# LPCB235_-_HE_ISO_CHANNEL.net
KiCad netlist of a schematic drawn in Altium Designer
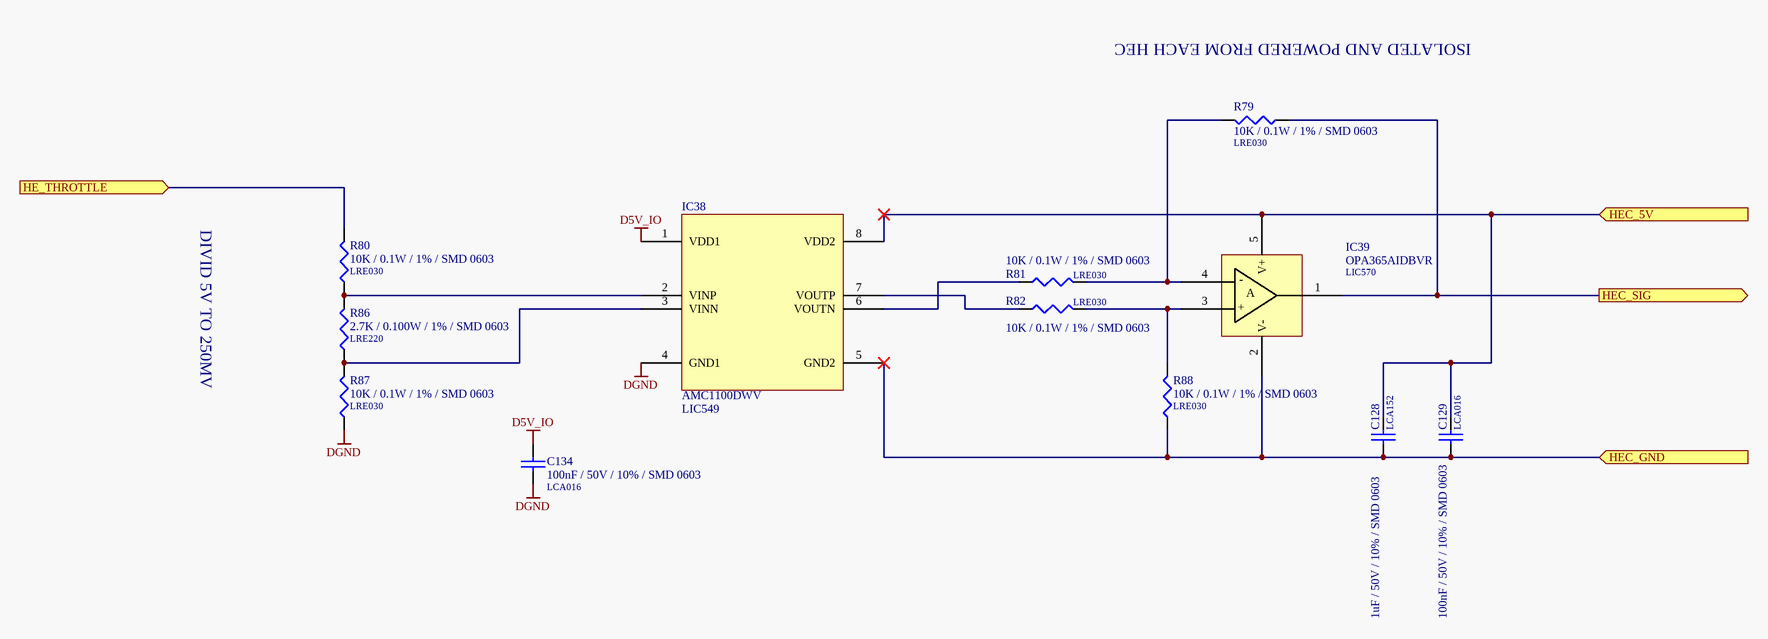
[diagram p0: LPCB235 - HE ISO CHANNEL.SchDoc]

(export (version "E")
  (design (tool "Eeschema 10.0.6"))
  (components
    (comp (ref "C128")
      (value "1uF / 50V / 10% / SMD 0603")
      (footprint "LFP011__CC1608-0603-IPC7351_B")
      (description "Capacitor, Ceramic Chip, 1uF, 50V, 10% (X5R), SMD 0603 [LCA152]")
      (fields (field (name "LDL_NUMBER") "LCA152"))
      (libsource (lib "LDL_Capacitors") (part "1uF / 50V / 10% / SMD 0603"))
    )
    (comp (ref "C129")
      (value "100nF / 50V / 10% / SMD 0603")
      (footprint "LFP011__CC1608-0603-IPC7351_B")
      (description "Capacitor, Ceramic Chip, 100nF (0.1uF), 50V, 5%, SMD 0603 [LCA016]")
      (fields (field (name "LDL_NUMBER") "LCA016"))
      (libsource (lib "LDL_Capacitors") (part "100nF / 50V / 10% / SMD 0603"))
    )
    (comp (ref "C134")
      (value "100nF / 50V / 10% / SMD 0603")
      (footprint "LFP011__CC1608-0603-IPC7351_B")
      (description "Capacitor, Ceramic Chip, 100nF (0.1uF), 50V, 5%, SMD 0603 [LCA016]")
      (fields (field (name "LDL_NUMBER") "LCA016"))
      (libsource (lib "LDL_Capacitors") (part "100nF / 50V / 10% / SMD 0603"))
    )
    (comp (ref "IC38")
      (value "AMC1100DWV")
      (footprint "LFP150__DWV0008A")
      (description "IC, Isolation Amplifier, SMD SOIC8 [LIC549]")
      (fields (field (name "LDL_NUMBER") "LIC549"))
      (libsource (lib "LDL_Semiconductors") (part "AMC1100DWV"))
    )
    (comp (ref "IC39")
      (value "OPA365AIDBVR")
      (footprint "LFP114__R-PDSO-G5")
      (description "IC, OpAmp, 1-Channel, Low Noise, SMD SOT-23-5 [LIC570]")
      (fields (field (name "LDL_NUMBER") "LIC570"))
      (libsource (lib "LDL_Semiconductors") (part "OPA365AIDBVR"))
    )
    (comp (ref "R79")
      (value "10K / 0.1W / 1% / SMD 0603")
      (footprint "LFP020__CR1608-0603-IPC7351_B")
      (description "Resistor, Ceramic Chip, 10K, 0.1W, 1%, SMD 0603 [LRE030]")
      (fields (field (name "LDL_NUMBER") "LRE030"))
      (libsource (lib "LDL_Resistors") (part "10K / 0.1W / 1% / SMD 0603"))
    )
    (comp (ref "R80")
      (value "10K / 0.1W / 1% / SMD 0603")
      (footprint "LFP020__CR1608-0603-IPC7351_B")
      (description "Resistor, Ceramic Chip, 10K, 0.1W, 1%, SMD 0603 [LRE030]")
      (fields (field (name "LDL_NUMBER") "LRE030"))
      (libsource (lib "LDL_Resistors") (part "10K / 0.1W / 1% / SMD 0603"))
    )
    (comp (ref "R81")
      (value "10K / 0.1W / 1% / SMD 0603")
      (footprint "LFP020__CR1608-0603-IPC7351_B")
      (description "Resistor, Ceramic Chip, 10K, 0.1W, 1%, SMD 0603 [LRE030]")
      (fields (field (name "LDL_NUMBER") "LRE030"))
      (libsource (lib "LDL_Resistors") (part "10K / 0.1W / 1% / SMD 0603"))
    )
    (comp (ref "R82")
      (value "10K / 0.1W / 1% / SMD 0603")
      (footprint "LFP020__CR1608-0603-IPC7351_B")
      (description "Resistor, Ceramic Chip, 10K, 0.1W, 1%, SMD 0603 [LRE030]")
      (fields (field (name "LDL_NUMBER") "LRE030"))
      (libsource (lib "LDL_Resistors") (part "10K / 0.1W / 1% / SMD 0603"))
    )
    (comp (ref "R86")
      (value "2.7K / 0.100W / 1% / SMD 0603")
      (footprint "LFP020__CR1608-0603-IPC7351_B")
      (description "Resistor, Thick Film, 2.7K, 0.100W, 75V, 1%, SMD 0603 [LRE220]")
      (fields (field (name "LDL_NUMBER") "LRE220"))
      (libsource (lib "LDL_Resistors") (part "2.7K / 0.100W / 1% / SMD 0603"))
    )
    (comp (ref "R87")
      (value "10K / 0.1W / 1% / SMD 0603")
      (footprint "LFP020__CR1608-0603-IPC7351_B")
      (description "Resistor, Ceramic Chip, 10K, 0.1W, 1%, SMD 0603 [LRE030]")
      (fields (field (name "LDL_NUMBER") "LRE030"))
      (libsource (lib "LDL_Resistors") (part "10K / 0.1W / 1% / SMD 0603"))
    )
    (comp (ref "R88")
      (value "10K / 0.1W / 1% / SMD 0603")
      (footprint "LFP020__CR1608-0603-IPC7351_B")
      (description "Resistor, Ceramic Chip, 10K, 0.1W, 1%, SMD 0603 [LRE030]")
      (fields (field (name "LDL_NUMBER") "LRE030"))
      (libsource (lib "LDL_Resistors") (part "10K / 0.1W / 1% / SMD 0603"))
    )
  )
  (nets
    (net (code "1") (name "/HEC_5V") (class "Default")
      (node (ref "C128") (pin "1") (pintype "passive"))
      (node (ref "C129") (pin "1") (pintype "passive"))
      (node (ref "IC38") (pin "8") (pinfunction "VDD2_8") (pintype "power_in"))
      (node (ref "IC39") (pin "5") (pinfunction "V+_5") (pintype "passive"))
    )
    (net (code "2") (name "/HEC_GND") (class "Default")
      (node (ref "C128") (pin "2") (pintype "passive"))
      (node (ref "C129") (pin "2") (pintype "passive"))
      (node (ref "IC38") (pin "5") (pinfunction "GND2_5") (pintype "power_in"))
      (node (ref "IC39") (pin "2") (pinfunction "V-_2") (pintype "passive"))
      (node (ref "R88") (pin "1") (pintype "passive"))
    )
    (net (code "3") (name "/HEC_SIG") (class "Default")
      (node (ref "IC39") (pin "1") (pinfunction "OUT_A_1") (pintype "passive"))
      (node (ref "R79") (pin "1") (pintype "passive"))
    )
    (net (code "4") (name "/HE_THROTTLE") (class "Default") (node (ref "R80") (pin "2") (pintype "passive")))
    (net (code "5") (name "D5V_IO") (class "Default")
      (node (ref "C134") (pin "1") (pintype "passive"))
      (node (ref "IC38") (pin "1") (pinfunction "VDD1_1") (pintype "power_in"))
    )
    (net (code "6") (name "DGND") (class "Default")
      (node (ref "C134") (pin "2") (pintype "passive"))
      (node (ref "IC38") (pin "4") (pinfunction "GND1_4") (pintype "power_in"))
      (node (ref "R87") (pin "1") (pintype "passive"))
    )
    (net (code "7") (name "Net-(IC38-VINN)") (class "Default")
      (node (ref "IC38") (pin "3") (pinfunction "VINN_3") (pintype "passive"))
      (node (ref "R86") (pin "1") (pintype "passive"))
      (node (ref "R87") (pin "2") (pintype "passive"))
    )
    (net (code "8") (name "Net-(IC38-VINP)") (class "Default")
      (node (ref "IC38") (pin "2") (pinfunction "VINP_2") (pintype "passive"))
      (node (ref "R80") (pin "1") (pintype "passive"))
      (node (ref "R86") (pin "2") (pintype "passive"))
    )
    (net (code "9") (name "Net-(IC38-VOUTN)") (class "Default")
      (node (ref "IC38") (pin "6") (pinfunction "VOUTN_6") (pintype "passive"))
      (node (ref "R81") (pin "1") (pintype "passive"))
    )
    (net (code "10") (name "Net-(IC38-VOUTP)") (class "Default")
      (node (ref "IC38") (pin "7") (pinfunction "VOUTP_7") (pintype "passive"))
      (node (ref "R82") (pin "1") (pintype "passive"))
    )
    (net (code "11") (name "Net-(IC39-+IN_A)") (class "Default")
      (node (ref "IC39") (pin "3") (pinfunction "+IN_A_3") (pintype "passive"))
      (node (ref "R82") (pin "2") (pintype "passive"))
      (node (ref "R88") (pin "2") (pintype "passive"))
    )
    (net (code "12") (name "Net-(IC39--IN_A)") (class "Default")
      (node (ref "IC39") (pin "4") (pinfunction "-IN_A_4") (pintype "passive"))
      (node (ref "R79") (pin "2") (pintype "passive"))
      (node (ref "R81") (pin "2") (pintype "passive"))
    )
  )
)
